# JiaB.net
KiCad netlist of a schematic drawn in EAGLE
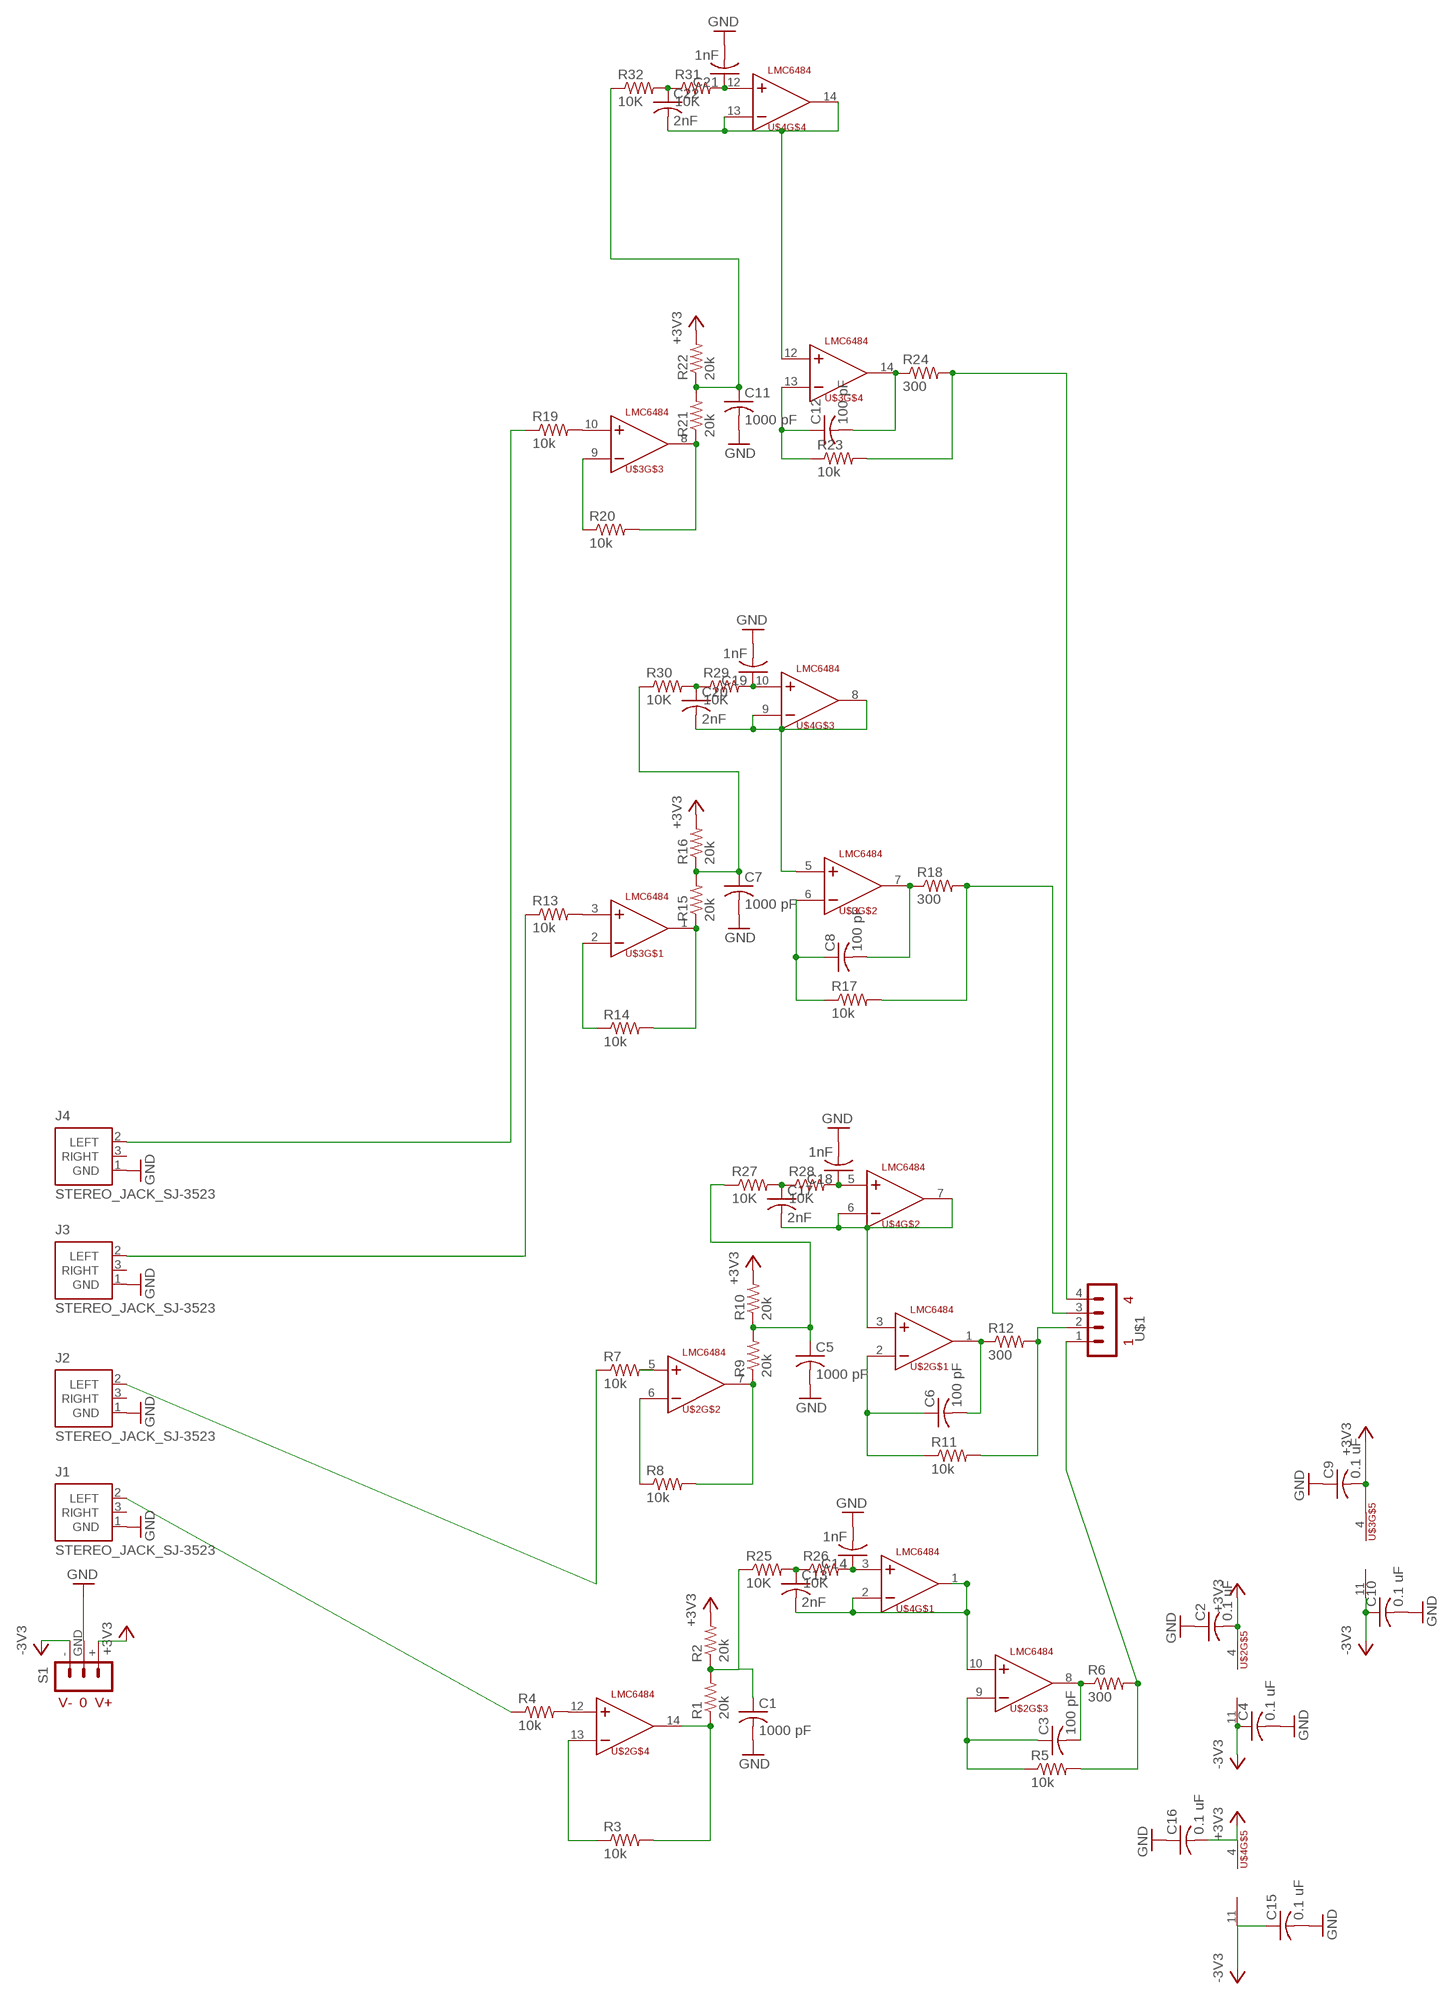
[diagram p0: schematic, sheet 1]

(export (version "E")
  (design (tool "Eeschema 10.0.6"))
  (components
    (comp (ref "C1")
      (value "1000 pF")
      (footprint "eagle-import:C025-025X050")
      (libsource (lib "eagle-import") (part "resistor_C-US025-025X050"))
    )
    (comp (ref "C2")
      (value "0.1 uF")
      (footprint "eagle-import:C025-025X050")
      (libsource (lib "eagle-import") (part "resistor_C-US025-025X050"))
    )
    (comp (ref "C3")
      (value "100 pF")
      (footprint "eagle-import:C025-025X050")
      (libsource (lib "eagle-import") (part "resistor_C-US025-025X050"))
    )
    (comp (ref "C4")
      (value "0.1 uF")
      (footprint "eagle-import:C025-025X050")
      (libsource (lib "eagle-import") (part "resistor_C-US025-025X050"))
    )
    (comp (ref "C5")
      (value "1000 pF")
      (footprint "eagle-import:C025-025X050")
      (libsource (lib "eagle-import") (part "resistor_C-US025-025X050"))
    )
    (comp (ref "C6")
      (value "100 pF")
      (footprint "eagle-import:C025-025X050")
      (libsource (lib "eagle-import") (part "resistor_C-US025-025X050"))
    )
    (comp (ref "C7")
      (value "1000 pF")
      (footprint "eagle-import:C025-025X050")
      (libsource (lib "eagle-import") (part "resistor_C-US025-025X050"))
    )
    (comp (ref "C8")
      (value "100 pF")
      (footprint "eagle-import:C025-025X050")
      (libsource (lib "eagle-import") (part "resistor_C-US025-025X050"))
    )
    (comp (ref "C9")
      (value "0.1 uF")
      (footprint "eagle-import:C025-025X050")
      (libsource (lib "eagle-import") (part "resistor_C-US025-025X050"))
    )
    (comp (ref "C10")
      (value "0.1 uF")
      (footprint "eagle-import:C025-025X050")
      (libsource (lib "eagle-import") (part "resistor_C-US025-025X050"))
    )
    (comp (ref "C11")
      (value "1000 pF")
      (footprint "eagle-import:C025-025X050")
      (libsource (lib "eagle-import") (part "resistor_C-US025-025X050"))
    )
    (comp (ref "C12")
      (value "100 pF")
      (footprint "eagle-import:C025-025X050")
      (libsource (lib "eagle-import") (part "resistor_C-US025-025X050"))
    )
    (comp (ref "C13")
      (value "2nF")
      (footprint "eagle-import:C025-025X050")
      (libsource (lib "eagle-import") (part "C-US025-025X050"))
    )
    (comp (ref "C14")
      (value "1nF")
      (footprint "eagle-import:C025-025X050")
      (libsource (lib "eagle-import") (part "C-US025-025X050"))
    )
    (comp (ref "C15")
      (value "0.1 uF")
      (footprint "eagle-import:C025-025X050")
      (libsource (lib "eagle-import") (part "resistor_C-US025-025X050"))
    )
    (comp (ref "C16")
      (value "0.1 uF")
      (footprint "eagle-import:C025-025X050")
      (libsource (lib "eagle-import") (part "resistor_C-US025-025X050"))
    )
    (comp (ref "C17")
      (value "2nF")
      (footprint "eagle-import:C025-025X050")
      (libsource (lib "eagle-import") (part "C-US025-025X050"))
    )
    (comp (ref "C18")
      (value "1nF")
      (footprint "eagle-import:C025-025X050")
      (libsource (lib "eagle-import") (part "C-US025-025X050"))
    )
    (comp (ref "C19")
      (value "1nF")
      (footprint "eagle-import:C025-025X050")
      (libsource (lib "eagle-import") (part "C-US025-025X050"))
    )
    (comp (ref "C20")
      (value "2nF")
      (footprint "eagle-import:C025-025X050")
      (libsource (lib "eagle-import") (part "C-US025-025X050"))
    )
    (comp (ref "C21")
      (value "1nF")
      (footprint "eagle-import:C025-025X050")
      (libsource (lib "eagle-import") (part "C-US025-025X050"))
    )
    (comp (ref "C22")
      (value "2nF")
      (footprint "eagle-import:C025-025X050")
      (libsource (lib "eagle-import") (part "C-US025-025X050"))
    )
    (comp (ref "J1")
      (value "STEREO_JACK_SJ-3523")
      (footprint "eagle-import:SJ-3523")
      (libsource (lib "eagle-import") (part "STEREO_JACK_SJ-3523"))
    )
    (comp (ref "J2")
      (value "STEREO_JACK_SJ-3523")
      (footprint "eagle-import:SJ-3523")
      (libsource (lib "eagle-import") (part "STEREO_JACK_SJ-3523"))
    )
    (comp (ref "J3")
      (value "STEREO_JACK_SJ-3523")
      (footprint "eagle-import:SJ-3523")
      (libsource (lib "eagle-import") (part "STEREO_JACK_SJ-3523"))
    )
    (comp (ref "J4")
      (value "STEREO_JACK_SJ-3523")
      (footprint "eagle-import:SJ-3523")
      (libsource (lib "eagle-import") (part "STEREO_JACK_SJ-3523"))
    )
    (comp (ref "R1")
      (value "20k")
      (footprint "eagle-import:0204_7")
      (libsource (lib "eagle-import") (part "resistor_R-US_0204/7"))
    )
    (comp (ref "R2")
      (value "20k")
      (footprint "eagle-import:0204_7")
      (libsource (lib "eagle-import") (part "resistor_R-US_0204/7"))
    )
    (comp (ref "R3")
      (value "10k")
      (footprint "eagle-import:0204_7")
      (libsource (lib "eagle-import") (part "resistor_R-US_0204/7"))
    )
    (comp (ref "R4")
      (value "10k")
      (footprint "eagle-import:0204_7")
      (libsource (lib "eagle-import") (part "resistor_R-US_0204/7"))
    )
    (comp (ref "R5")
      (value "10k")
      (footprint "eagle-import:0204_7")
      (libsource (lib "eagle-import") (part "resistor_R-US_0204/7"))
    )
    (comp (ref "R6")
      (value "300")
      (footprint "eagle-import:0204_7")
      (libsource (lib "eagle-import") (part "resistor_R-US_0204/7"))
    )
    (comp (ref "R7")
      (value "10k")
      (footprint "eagle-import:0204_7")
      (libsource (lib "eagle-import") (part "resistor_R-US_0204/7"))
    )
    (comp (ref "R8")
      (value "10k")
      (footprint "eagle-import:0204_7")
      (libsource (lib "eagle-import") (part "resistor_R-US_0204/7"))
    )
    (comp (ref "R9")
      (value "20k")
      (footprint "eagle-import:0204_7")
      (libsource (lib "eagle-import") (part "resistor_R-US_0204/7"))
    )
    (comp (ref "R10")
      (value "20k")
      (footprint "eagle-import:0204_7")
      (libsource (lib "eagle-import") (part "resistor_R-US_0204/7"))
    )
    (comp (ref "R11")
      (value "10k")
      (footprint "eagle-import:0204_7")
      (libsource (lib "eagle-import") (part "resistor_R-US_0204/7"))
    )
    (comp (ref "R12")
      (value "300")
      (footprint "eagle-import:0204_7")
      (libsource (lib "eagle-import") (part "resistor_R-US_0204/7"))
    )
    (comp (ref "R13")
      (value "10k")
      (footprint "eagle-import:0204_7")
      (libsource (lib "eagle-import") (part "resistor_R-US_0204/7"))
    )
    (comp (ref "R14")
      (value "10k")
      (footprint "eagle-import:0204_7")
      (libsource (lib "eagle-import") (part "resistor_R-US_0204/7"))
    )
    (comp (ref "R15")
      (value "20k")
      (footprint "eagle-import:0204_7")
      (libsource (lib "eagle-import") (part "resistor_R-US_0204/7"))
    )
    (comp (ref "R16")
      (value "20k")
      (footprint "eagle-import:0204_7")
      (libsource (lib "eagle-import") (part "resistor_R-US_0204/7"))
    )
    (comp (ref "R17")
      (value "10k")
      (footprint "eagle-import:0204_7")
      (libsource (lib "eagle-import") (part "resistor_R-US_0204/7"))
    )
    (comp (ref "R18")
      (value "300")
      (footprint "eagle-import:0204_7")
      (libsource (lib "eagle-import") (part "resistor_R-US_0204/7"))
    )
    (comp (ref "R19")
      (value "10k")
      (footprint "eagle-import:0204_7")
      (libsource (lib "eagle-import") (part "resistor_R-US_0204/7"))
    )
    (comp (ref "R20")
      (value "10k")
      (footprint "eagle-import:0204_7")
      (libsource (lib "eagle-import") (part "resistor_R-US_0204/7"))
    )
    (comp (ref "R21")
      (value "20k")
      (footprint "eagle-import:0204_7")
      (libsource (lib "eagle-import") (part "resistor_R-US_0204/7"))
    )
    (comp (ref "R22")
      (value "20k")
      (footprint "eagle-import:0204_7")
      (libsource (lib "eagle-import") (part "resistor_R-US_0204/7"))
    )
    (comp (ref "R23")
      (value "10k")
      (footprint "eagle-import:0204_7")
      (libsource (lib "eagle-import") (part "resistor_R-US_0204/7"))
    )
    (comp (ref "R24")
      (value "300")
      (footprint "eagle-import:0204_7")
      (libsource (lib "eagle-import") (part "resistor_R-US_0204/7"))
    )
    (comp (ref "R25")
      (value "10K")
      (footprint "eagle-import:0204_7")
      (libsource (lib "eagle-import") (part "R-US_0204/7"))
    )
    (comp (ref "R26")
      (value "10K")
      (footprint "eagle-import:0204_7")
      (libsource (lib "eagle-import") (part "R-US_0204/7"))
    )
    (comp (ref "R27")
      (value "10K")
      (footprint "eagle-import:0204_7")
      (libsource (lib "eagle-import") (part "R-US_0204/7"))
    )
    (comp (ref "R28")
      (value "10K")
      (footprint "eagle-import:0204_7")
      (libsource (lib "eagle-import") (part "R-US_0204/7"))
    )
    (comp (ref "R29")
      (value "10K")
      (footprint "eagle-import:0204_7")
      (libsource (lib "eagle-import") (part "R-US_0204/7"))
    )
    (comp (ref "R30")
      (value "10K")
      (footprint "eagle-import:0204_7")
      (libsource (lib "eagle-import") (part "R-US_0204/7"))
    )
    (comp (ref "R31")
      (value "10K")
      (footprint "eagle-import:0204_7")
      (libsource (lib "eagle-import") (part "R-US_0204/7"))
    )
    (comp (ref "R32")
      (value "10K")
      (footprint "eagle-import:0204_7")
      (libsource (lib "eagle-import") (part "R-US_0204/7"))
    )
    (comp (ref "S1")
      (value "TERMINAL_BLOCK_3_+/-3.3V")
      (footprint "eagle-import:TERMINAL_BLOCK_3.5MM_3")
      (libsource (lib "eagle-import") (part "TERMINAL_BLOCK_3_+/-3.3V"))
    )
    (comp (ref "U$1")
      (value "TERMINAL-BLOCK-4")
      (footprint "eagle-import:TERMINAL-BLOCK-4")
      (libsource (lib "eagle-import") (part "TERMINAL-BLOCK-4"))
    )
    (comp (ref "U$2")
      (value "LMC6484")
      (footprint "eagle-import:DIL14")
      (libsource (lib "eagle-import") (part "LMC6484"))
    )
    (comp (ref "U$3")
      (value "LMC6484")
      (footprint "eagle-import:DIL14")
      (libsource (lib "eagle-import") (part "LMC6484"))
    )
    (comp (ref "U$4")
      (value "LMC6484")
      (footprint "eagle-import:DIL14")
      (libsource (lib "eagle-import") (part "LMC6484"))
    )
  )
  (nets
    (net (code "1") (name "+3V3") (class "Default")
      (node (ref "C16") (pin "2") (pinfunction "2_2") (pintype "passive"))
      (node (ref "C2") (pin "2") (pinfunction "2_2") (pintype "passive"))
      (node (ref "C9") (pin "2") (pinfunction "2_2") (pintype "passive"))
      (node (ref "R10") (pin "2") (pinfunction "2_2") (pintype "passive"))
      (node (ref "R16") (pin "2") (pinfunction "2_2") (pintype "passive"))
      (node (ref "R2") (pin "2") (pinfunction "2_2") (pintype "passive"))
      (node (ref "R22") (pin "2") (pinfunction "2_2") (pintype "passive"))
      (node (ref "S1") (pin "+") (pinfunction "+_+") (pintype "passive"))
      (node (ref "U$2") (pin "4") (pinfunction "VCC+_4") (pintype "power_in"))
      (node (ref "U$3") (pin "4") (pinfunction "VCC+_4") (pintype "power_in"))
      (node (ref "U$4") (pin "4") (pinfunction "VCC+_4") (pintype "power_in"))
    )
    (net (code "2") (name "-3V3") (class "Default")
      (node (ref "C10") (pin "1") (pinfunction "1_1") (pintype "passive"))
      (node (ref "C15") (pin "1") (pinfunction "1_1") (pintype "passive"))
      (node (ref "C4") (pin "1") (pinfunction "1_1") (pintype "passive"))
      (node (ref "S1") (pin "-") (pinfunction "-_-") (pintype "passive"))
      (node (ref "U$2") (pin "11") (pinfunction "VCC-_11") (pintype "power_in"))
      (node (ref "U$3") (pin "11") (pinfunction "VCC-_11") (pintype "power_in"))
      (node (ref "U$4") (pin "11") (pinfunction "VCC-_11") (pintype "power_in"))
    )
    (net (code "3") (name "GND") (class "Default")
      (node (ref "C1") (pin "2") (pinfunction "2_2") (pintype "passive"))
      (node (ref "C10") (pin "2") (pinfunction "2_2") (pintype "passive"))
      (node (ref "C11") (pin "2") (pinfunction "2_2") (pintype "passive"))
      (node (ref "C14") (pin "2") (pinfunction "2_2") (pintype "passive"))
      (node (ref "C15") (pin "2") (pinfunction "2_2") (pintype "passive"))
      (node (ref "C16") (pin "1") (pinfunction "1_1") (pintype "passive"))
      (node (ref "C18") (pin "2") (pinfunction "2_2") (pintype "passive"))
      (node (ref "C19") (pin "2") (pinfunction "2_2") (pintype "passive"))
      (node (ref "C2") (pin "1") (pinfunction "1_1") (pintype "passive"))
      (node (ref "C21") (pin "2") (pinfunction "2_2") (pintype "passive"))
      (node (ref "C4") (pin "2") (pinfunction "2_2") (pintype "passive"))
      (node (ref "C5") (pin "2") (pinfunction "2_2") (pintype "passive"))
      (node (ref "C7") (pin "2") (pinfunction "2_2") (pintype "passive"))
      (node (ref "C9") (pin "1") (pinfunction "1_1") (pintype "passive"))
      (node (ref "J1") (pin "1") (pinfunction "GND_1") (pintype "power_in"))
      (node (ref "J2") (pin "1") (pinfunction "GND_1") (pintype "power_in"))
      (node (ref "J3") (pin "1") (pinfunction "GND_1") (pintype "power_in"))
      (node (ref "J4") (pin "1") (pinfunction "GND_1") (pintype "power_in"))
      (node (ref "S1") (pin "GND") (pinfunction "GND_GND") (pintype "passive"))
    )
    (net (code "4") (name "Net-(C1-Pad1)") (class "Default")
      (node (ref "C1") (pin "1") (pinfunction "1_1") (pintype "passive"))
      (node (ref "R1") (pin "2") (pinfunction "2_2") (pintype "passive"))
      (node (ref "R2") (pin "1") (pinfunction "1_1") (pintype "passive"))
      (node (ref "R25") (pin "1") (pinfunction "1_1") (pintype "passive"))
    )
    (net (code "5") (name "Net-(C5-Pad1)") (class "Default")
      (node (ref "C5") (pin "1") (pinfunction "1_1") (pintype "passive"))
      (node (ref "R10") (pin "1") (pinfunction "1_1") (pintype "passive"))
      (node (ref "R27") (pin "1") (pinfunction "1_1") (pintype "passive"))
      (node (ref "R9") (pin "2") (pinfunction "2_2") (pintype "passive"))
    )
    (net (code "6") (name "Net-(C7-Pad1)") (class "Default")
      (node (ref "C7") (pin "1") (pinfunction "1_1") (pintype "passive"))
      (node (ref "R15") (pin "2") (pinfunction "2_2") (pintype "passive"))
      (node (ref "R16") (pin "1") (pinfunction "1_1") (pintype "passive"))
      (node (ref "R30") (pin "1") (pinfunction "1_1") (pintype "passive"))
    )
    (net (code "7") (name "Net-(C11-Pad1)") (class "Default")
      (node (ref "C11") (pin "1") (pinfunction "1_1") (pintype "passive"))
      (node (ref "R21") (pin "2") (pinfunction "2_2") (pintype "passive"))
      (node (ref "R22") (pin "1") (pinfunction "1_1") (pintype "passive"))
      (node (ref "R32") (pin "1") (pinfunction "1_1") (pintype "passive"))
    )
    (net (code "8") (name "Net-(C13-Pad1)") (class "Default")
      (node (ref "C13") (pin "1") (pinfunction "1_1") (pintype "passive"))
      (node (ref "R25") (pin "2") (pinfunction "2_2") (pintype "passive"))
      (node (ref "R26") (pin "1") (pinfunction "1_1") (pintype "passive"))
    )
    (net (code "9") (name "Net-(C17-Pad1)") (class "Default")
      (node (ref "C17") (pin "1") (pinfunction "1_1") (pintype "passive"))
      (node (ref "R27") (pin "2") (pinfunction "2_2") (pintype "passive"))
      (node (ref "R28") (pin "1") (pinfunction "1_1") (pintype "passive"))
    )
    (net (code "10") (name "Net-(C20-Pad1)") (class "Default")
      (node (ref "C20") (pin "1") (pinfunction "1_1") (pintype "passive"))
      (node (ref "R29") (pin "1") (pinfunction "1_1") (pintype "passive"))
      (node (ref "R30") (pin "2") (pinfunction "2_2") (pintype "passive"))
    )
    (net (code "11") (name "Net-(C22-Pad1)") (class "Default")
      (node (ref "C22") (pin "1") (pinfunction "1_1") (pintype "passive"))
      (node (ref "R31") (pin "1") (pinfunction "1_1") (pintype "passive"))
      (node (ref "R32") (pin "2") (pinfunction "2_2") (pintype "passive"))
    )
    (net (code "12") (name "Net-(J1-LEFT)") (class "Default")
      (node (ref "J1") (pin "2") (pinfunction "LEFT_2") (pintype "output"))
      (node (ref "R4") (pin "1") (pinfunction "1_1") (pintype "passive"))
    )
    (net (code "13") (name "Net-(J2-LEFT)") (class "Default")
      (node (ref "J2") (pin "2") (pinfunction "LEFT_2") (pintype "output"))
      (node (ref "R7") (pin "1") (pinfunction "1_1") (pintype "passive"))
    )
    (net (code "14") (name "Net-(J3-LEFT)") (class "Default")
      (node (ref "J3") (pin "2") (pinfunction "LEFT_2") (pintype "output"))
      (node (ref "R13") (pin "1") (pinfunction "1_1") (pintype "passive"))
    )
    (net (code "15") (name "Net-(J4-LEFT)") (class "Default")
      (node (ref "J4") (pin "2") (pinfunction "LEFT_2") (pintype "output"))
      (node (ref "R19") (pin "1") (pinfunction "1_1") (pintype "passive"))
    )
    (net (code "16") (name "Net-(R5-Pad2)") (class "Default")
      (node (ref "R5") (pin "2") (pinfunction "2_2") (pintype "passive"))
      (node (ref "R6") (pin "2") (pinfunction "2_2") (pintype "passive"))
      (node (ref "U$1") (pin "1") (pinfunction "1_1") (pintype "passive"))
    )
    (net (code "17") (name "Net-(R11-Pad2)") (class "Default")
      (node (ref "R11") (pin "2") (pinfunction "2_2") (pintype "passive"))
      (node (ref "R12") (pin "2") (pinfunction "2_2") (pintype "passive"))
      (node (ref "U$1") (pin "2") (pinfunction "2_2") (pintype "passive"))
    )
    (net (code "18") (name "Net-(R17-Pad2)") (class "Default")
      (node (ref "R17") (pin "2") (pinfunction "2_2") (pintype "passive"))
      (node (ref "R18") (pin "2") (pinfunction "2_2") (pintype "passive"))
      (node (ref "U$1") (pin "3") (pinfunction "3_3") (pintype "passive"))
    )
    (net (code "19") (name "Net-(R23-Pad2)") (class "Default")
      (node (ref "R23") (pin "2") (pinfunction "2_2") (pintype "passive"))
      (node (ref "R24") (pin "2") (pinfunction "2_2") (pintype "passive"))
      (node (ref "U$1") (pin "4") (pinfunction "4_4") (pintype "passive"))
    )
    (net (code "20") (name "Net-(U$2A-IN+)") (class "Default")
      (node (ref "C17") (pin "2") (pinfunction "2_2") (pintype "passive"))
      (node (ref "U$2") (pin "3") (pinfunction "IN+_3") (pintype "input"))
      (node (ref "U$4") (pin "6") (pinfunction "IN-_6") (pintype "input"))
      (node (ref "U$4") (pin "7") (pinfunction "OUT_7") (pintype "output"))
    )
    (net (code "21") (name "Net-(U$2A-IN-)") (class "Default")
      (node (ref "C6") (pin "1") (pinfunction "1_1") (pintype "passive"))
      (node (ref "R11") (pin "1") (pinfunction "1_1") (pintype "passive"))
      (node (ref "U$2") (pin "2") (pinfunction "IN-_2") (pintype "input"))
    )
    (net (code "22") (name "Net-(U$2A-OUT)") (class "Default")
      (node (ref "C6") (pin "2") (pinfunction "2_2") (pintype "passive"))
      (node (ref "R12") (pin "1") (pinfunction "1_1") (pintype "passive"))
      (node (ref "U$2") (pin "1") (pinfunction "OUT_1") (pintype "output"))
    )
    (net (code "23") (name "Net-(U$2B-IN+)") (class "Default")
      (node (ref "R7") (pin "2") (pinfunction "2_2") (pintype "passive"))
      (node (ref "U$2") (pin "5") (pinfunction "IN+_5") (pintype "input"))
    )
    (net (code "24") (name "Net-(U$2B-IN-)") (class "Default")
      (node (ref "R8") (pin "1") (pinfunction "1_1") (pintype "passive"))
      (node (ref "U$2") (pin "6") (pinfunction "IN-_6") (pintype "input"))
    )
    (net (code "25") (name "Net-(U$2B-OUT)") (class "Default")
      (node (ref "R8") (pin "2") (pinfunction "2_2") (pintype "passive"))
      (node (ref "R9") (pin "1") (pinfunction "1_1") (pintype "passive"))
      (node (ref "U$2") (pin "7") (pinfunction "OUT_7") (pintype "output"))
    )
    (net (code "26") (name "Net-(U$2C-IN+)") (class "Default")
      (node (ref "C13") (pin "2") (pinfunction "2_2") (pintype "passive"))
      (node (ref "U$2") (pin "10") (pinfunction "IN+_10") (pintype "input"))
      (node (ref "U$4") (pin "1") (pinfunction "OUT_1") (pintype "output"))
      (node (ref "U$4") (pin "2") (pinfunction "IN-_2") (pintype "input"))
    )
    (net (code "27") (name "Net-(U$2C-IN-)") (class "Default")
      (node (ref "C3") (pin "1") (pinfunction "1_1") (pintype "passive"))
      (node (ref "R5") (pin "1") (pinfunction "1_1") (pintype "passive"))
      (node (ref "U$2") (pin "9") (pinfunction "IN-_9") (pintype "input"))
    )
    (net (code "28") (name "Net-(U$2C-OUT)") (class "Default")
      (node (ref "C3") (pin "2") (pinfunction "2_2") (pintype "passive"))
      (node (ref "R6") (pin "1") (pinfunction "1_1") (pintype "passive"))
      (node (ref "U$2") (pin "8") (pinfunction "OUT_8") (pintype "output"))
    )
    (net (code "29") (name "Net-(U$2D-IN+)") (class "Default")
      (node (ref "R4") (pin "2") (pinfunction "2_2") (pintype "passive"))
      (node (ref "U$2") (pin "12") (pinfunction "IN+_12") (pintype "input"))
    )
    (net (code "30") (name "Net-(U$2D-IN-)") (class "Default")
      (node (ref "R3") (pin "1") (pinfunction "1_1") (pintype "passive"))
      (node (ref "U$2") (pin "13") (pinfunction "IN-_13") (pintype "input"))
    )
    (net (code "31") (name "Net-(U$2D-OUT)") (class "Default")
      (node (ref "R1") (pin "1") (pinfunction "1_1") (pintype "passive"))
      (node (ref "R3") (pin "2") (pinfunction "2_2") (pintype "passive"))
      (node (ref "U$2") (pin "14") (pinfunction "OUT_14") (pintype "output"))
    )
    (net (code "32") (name "Net-(U$3A-IN+)") (class "Default")
      (node (ref "R13") (pin "2") (pinfunction "2_2") (pintype "passive"))
      (node (ref "U$3") (pin "3") (pinfunction "IN+_3") (pintype "input"))
    )
    (net (code "33") (name "Net-(U$3A-IN-)") (class "Default")
      (node (ref "R14") (pin "1") (pinfunction "1_1") (pintype "passive"))
      (node (ref "U$3") (pin "2") (pinfunction "IN-_2") (pintype "input"))
    )
    (net (code "34") (name "Net-(U$3A-OUT)") (class "Default")
      (node (ref "R14") (pin "2") (pinfunction "2_2") (pintype "passive"))
      (node (ref "R15") (pin "1") (pinfunction "1_1") (pintype "passive"))
      (node (ref "U$3") (pin "1") (pinfunction "OUT_1") (pintype "output"))
    )
    (net (code "35") (name "Net-(U$3B-IN+)") (class "Default")
      (node (ref "C20") (pin "2") (pinfunction "2_2") (pintype "passive"))
      (node (ref "U$3") (pin "5") (pinfunction "IN+_5") (pintype "input"))
      (node (ref "U$4") (pin "8") (pinfunction "OUT_8") (pintype "output"))
      (node (ref "U$4") (pin "9") (pinfunction "IN-_9") (pintype "input"))
    )
    (net (code "36") (name "Net-(U$3B-IN-)") (class "Default")
      (node (ref "C8") (pin "1") (pinfunction "1_1") (pintype "passive"))
      (node (ref "R17") (pin "1") (pinfunction "1_1") (pintype "passive"))
      (node (ref "U$3") (pin "6") (pinfunction "IN-_6") (pintype "input"))
    )
    (net (code "37") (name "Net-(U$3B-OUT)") (class "Default")
      (node (ref "C8") (pin "2") (pinfunction "2_2") (pintype "passive"))
      (node (ref "R18") (pin "1") (pinfunction "1_1") (pintype "passive"))
      (node (ref "U$3") (pin "7") (pinfunction "OUT_7") (pintype "output"))
    )
    (net (code "38") (name "Net-(U$3C-IN+)") (class "Default")
      (node (ref "R19") (pin "2") (pinfunction "2_2") (pintype "passive"))
      (node (ref "U$3") (pin "10") (pinfunction "IN+_10") (pintype "input"))
    )
    (net (code "39") (name "Net-(U$3C-IN-)") (class "Default")
      (node (ref "R20") (pin "1") (pinfunction "1_1") (pintype "passive"))
      (node (ref "U$3") (pin "9") (pinfunction "IN-_9") (pintype "input"))
    )
    (net (code "40") (name "Net-(U$3C-OUT)") (class "Default")
      (node (ref "R20") (pin "2") (pinfunction "2_2") (pintype "passive"))
      (node (ref "R21") (pin "1") (pinfunction "1_1") (pintype "passive"))
      (node (ref "U$3") (pin "8") (pinfunction "OUT_8") (pintype "output"))
    )
    (net (code "41") (name "Net-(U$3D-IN+)") (class "Default")
      (node (ref "C22") (pin "2") (pinfunction "2_2") (pintype "passive"))
      (node (ref "U$3") (pin "12") (pinfunction "IN+_12") (pintype "input"))
      (node (ref "U$4") (pin "13") (pinfunction "IN-_13") (pintype "input"))
      (node (ref "U$4") (pin "14") (pinfunction "OUT_14") (pintype "output"))
    )
    (net (code "42") (name "Net-(U$3D-IN-)") (class "Default")
      (node (ref "C12") (pin "1") (pinfunction "1_1") (pintype "passive"))
      (node (ref "R23") (pin "1") (pinfunction "1_1") (pintype "passive"))
      (node (ref "U$3") (pin "13") (pinfunction "IN-_13") (pintype "input"))
    )
    (net (code "43") (name "Net-(U$3D-OUT)") (class "Default")
      (node (ref "C12") (pin "2") (pinfunction "2_2") (pintype "passive"))
      (node (ref "R24") (pin "1") (pinfunction "1_1") (pintype "passive"))
      (node (ref "U$3") (pin "14") (pinfunction "OUT_14") (pintype "output"))
    )
    (net (code "44") (name "Net-(U$4A-IN+)") (class "Default")
      (node (ref "C14") (pin "1") (pinfunction "1_1") (pintype "passive"))
      (node (ref "R26") (pin "2") (pinfunction "2_2") (pintype "passive"))
      (node (ref "U$4") (pin "3") (pinfunction "IN+_3") (pintype "input"))
    )
    (net (code "45") (name "Net-(U$4B-IN+)") (class "Default")
      (node (ref "C18") (pin "1") (pinfunction "1_1") (pintype "passive"))
      (node (ref "R28") (pin "2") (pinfunction "2_2") (pintype "passive"))
      (node (ref "U$4") (pin "5") (pinfunction "IN+_5") (pintype "input"))
    )
    (net (code "46") (name "Net-(U$4C-IN+)") (class "Default")
      (node (ref "C19") (pin "1") (pinfunction "1_1") (pintype "passive"))
      (node (ref "R29") (pin "2") (pinfunction "2_2") (pintype "passive"))
      (node (ref "U$4") (pin "10") (pinfunction "IN+_10") (pintype "input"))
    )
    (net (code "47") (name "Net-(U$4D-IN+)") (class "Default")
      (node (ref "C21") (pin "1") (pinfunction "1_1") (pintype "passive"))
      (node (ref "R31") (pin "2") (pinfunction "2_2") (pintype "passive"))
      (node (ref "U$4") (pin "12") (pinfunction "IN+_12") (pintype "input"))
    )
    (net (code "48") (name "unconnected-(J1-RIGHT-Pad3)") (class "Default")
      (node (ref "J1") (pin "3") (pinfunction "RIGHT_3") (pintype "output"))
    )
    (net (code "49") (name "unconnected-(J2-RIGHT-Pad3)") (class "Default")
      (node (ref "J2") (pin "3") (pinfunction "RIGHT_3") (pintype "output"))
    )
    (net (code "50") (name "unconnected-(J3-RIGHT-Pad3)") (class "Default")
      (node (ref "J3") (pin "3") (pinfunction "RIGHT_3") (pintype "output"))
    )
    (net (code "51") (name "unconnected-(J4-RIGHT-Pad3)") (class "Default")
      (node (ref "J4") (pin "3") (pinfunction "RIGHT_3") (pintype "output"))
    )
  )
)
